# MotorCell.net
KiCad netlist of a schematic drawn in Altium Designer
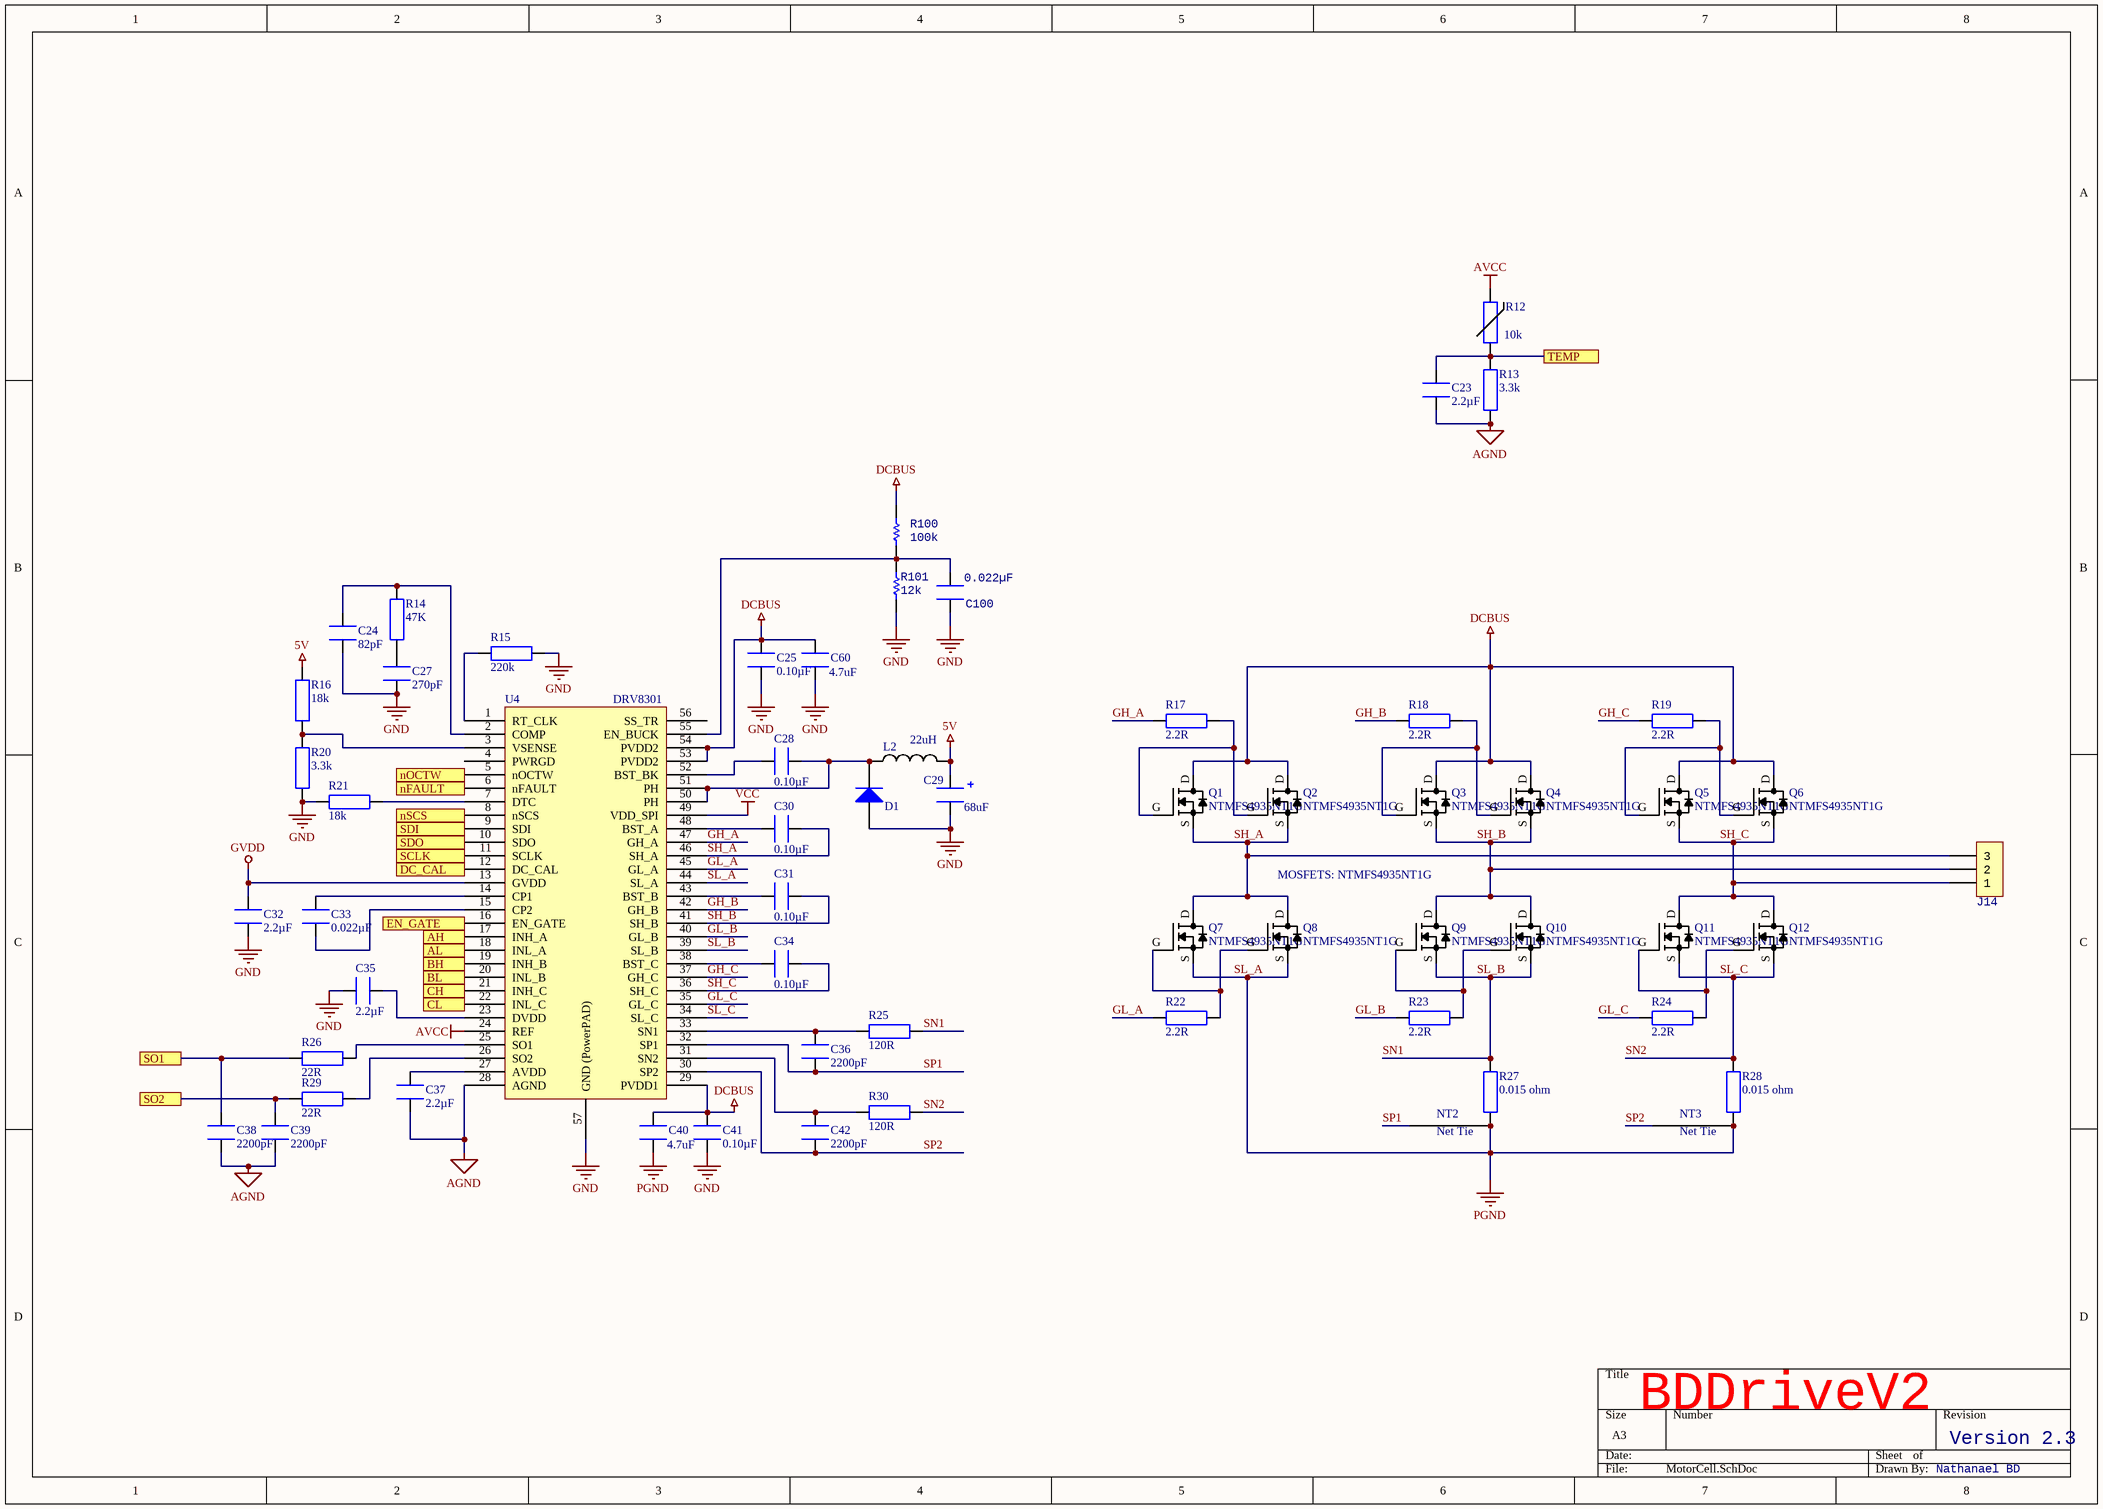
[diagram p0: MotorCell.SchDoc]

(export (version "E")
  (design (tool "Eeschema 10.0.6"))
  (components
    (comp (ref "C23")
      (value "2.2µF")
      (footprint "CAPC1608X09L")
      (description "CAP CER 2.2UF 16V X5R 0603")
      (fields
        (field (name "MANUFACTURER") "Murata Electronics North America")
        (field (name "MANUFACTURER PART NUMBER") "GRM188R61C225KE15D")
      )
      (libsource (lib "CustomComponents") (part "GRM188R61C225KE15D"))
    )
    (comp (ref "C24")
      (value "82pF")
      (footprint "CAPC1608X09L")
      (description "CAP CER 82PF 100V NP0 0603")
      (fields
        (field (name "MANUFACTURER") "Murata Electronics North America")
        (field (name "MANUFACTURER PART NUMBER") "GRM1885C2A820JA01D")
      )
      (libsource (lib "CustomComponents") (part "GRM1885C2A820JA01D"))
    )
    (comp (ref "C25")
      (value "0.10µF")
      (footprint "CAPC1608X09L")
      (description "CAP CER 0.1UF 25V X7R 0603")
      (fields
        (field (name "MANUFACTURER") "Murata Electronics North America")
        (field (name "MANUFACTURER PART NUMBER") "GRM188R71E104KA01D")
      )
      (libsource (lib "CustomComponents") (part "GRM188R71E104KA01D"))
    )
    (comp (ref "C27")
      (value "270pF")
      (footprint "CAPC1608X09L")
      (description "CAP CER 270PF 50V NP0 0603")
      (fields
        (field (name "MANUFACTURER") "Murata Electronics North America")
        (field (name "MANUFACTURER PART NUMBER") "GRM1885C1H271JA01D")
      )
      (libsource (lib "CustomComponents") (part "GRM1885C1H271JA01D"))
    )
    (comp (ref "C28")
      (value "0.10µF")
      (footprint "CAPC1608X09L")
      (description "CAP CER 0.1UF 25V X7R 0603")
      (fields
        (field (name "MANUFACTURER") "Murata Electronics North America")
        (field (name "MANUFACTURER PART NUMBER") "GRM188R71E104KA01D")
      )
      (libsource (lib "CustomComponents") (part "GRM188R71E104KA01D"))
    )
    (comp (ref "C29")
      (value "68uF")
      (footprint "CAPCP6032X28N")
      (description "CAP TANT 68UF 16V 20% 2312 250mOhm")
      (libsource (lib "CustomComponents") (part "T495C686M016ATE250"))
    )
    (comp (ref "C30")
      (value "0.10µF")
      (footprint "CAPC1608X09L")
      (description "CAP CER 0.1UF 25V X7R 0603")
      (fields
        (field (name "MANUFACTURER") "Murata Electronics North America")
        (field (name "MANUFACTURER PART NUMBER") "GRM188R71E104KA01D")
      )
      (libsource (lib "CustomComponents") (part "GRM188R71E104KA01D"))
    )
    (comp (ref "C31")
      (value "0.10µF")
      (footprint "CAPC1608X09L")
      (description "CAP CER 0.1UF 25V X7R 0603")
      (fields
        (field (name "MANUFACTURER") "Murata Electronics North America")
        (field (name "MANUFACTURER PART NUMBER") "GRM188R71E104KA01D")
      )
      (libsource (lib "CustomComponents") (part "GRM188R71E104KA01D"))
    )
    (comp (ref "C32")
      (value "2.2µF")
      (footprint "CAPC1608X09L")
      (description "CAP CER 2.2UF 16V X5R 0603")
      (fields
        (field (name "MANUFACTURER") "Murata Electronics North America")
        (field (name "MANUFACTURER PART NUMBER") "GRM188R61C225KE15D")
      )
      (libsource (lib "CustomComponents") (part "GRM188R61C225KE15D"))
    )
    (comp (ref "C33")
      (value "0.022µF")
      (footprint "CAPC1608X09L")
      (description "CAP CER 0.022UF 25V X7R 0603")
      (fields
        (field (name "MANUFACTURER") "Murata Electronics North America")
        (field (name "MANUFACTURER PART NUMBER") "GRM188R71E223KA01D")
      )
      (libsource (lib "CustomComponents") (part "GRM188R71E223KA01D"))
    )
    (comp (ref "C34")
      (value "0.10µF")
      (footprint "CAPC1608X09L")
      (description "CAP CER 0.1UF 25V X7R 0603")
      (fields
        (field (name "MANUFACTURER") "Murata Electronics North America")
        (field (name "MANUFACTURER PART NUMBER") "GRM188R71E104KA01D")
      )
      (libsource (lib "CustomComponents") (part "GRM188R71E104KA01D"))
    )
    (comp (ref "C35")
      (value "2.2µF")
      (footprint "CAPC1608X09L")
      (description "CAP CER 2.2UF 16V X5R 0603")
      (fields
        (field (name "MANUFACTURER") "Murata Electronics North America")
        (field (name "MANUFACTURER PART NUMBER") "GRM188R61C225KE15D")
      )
      (libsource (lib "CustomComponents") (part "GRM188R61C225KE15D"))
    )
    (comp (ref "C36")
      (value "2200pF")
      (footprint "CAPC1608X09L")
      (description "CAP CER 2200PF 50V NP0 0603")
      (fields
        (field (name "MANUFACTURER") "Murata Electronics North America")
        (field (name "TOLERANCE") "±5%")
      )
      (libsource (lib "CustomComponents") (part "GRM1885C1H222JA01D"))
    )
    (comp (ref "C37")
      (value "2.2µF")
      (footprint "CAPC1608X09L")
      (description "CAP CER 2.2UF 16V X5R 0603")
      (fields
        (field (name "MANUFACTURER") "Murata Electronics North America")
        (field (name "MANUFACTURER PART NUMBER") "GRM188R61C225KE15D")
      )
      (libsource (lib "CustomComponents") (part "GRM188R61C225KE15D"))
    )
    (comp (ref "C38")
      (value "2200pF")
      (footprint "CAPC1608X09L")
      (description "CAP CER 2200PF 50V NP0 0603")
      (fields
        (field (name "MANUFACTURER") "Murata Electronics North America")
        (field (name "TOLERANCE") "±5%")
      )
      (libsource (lib "CustomComponents") (part "GRM1885C1H222JA01D"))
    )
    (comp (ref "C39")
      (value "2200pF")
      (footprint "CAPC1608X09L")
      (description "CAP CER 2200PF 50V NP0 0603")
      (fields
        (field (name "MANUFACTURER") "Murata Electronics North America")
        (field (name "TOLERANCE") "±5%")
      )
      (libsource (lib "CustomComponents") (part "GRM1885C1H222JA01D"))
    )
    (comp (ref "C40")
      (value "4.7uF")
      (footprint "CAPC2012X09N")
      (description "CAP CER 4.7UF 35V X5R 0805")
      (libsource (lib "CustomComponents") (part "GRM219R6YA475KA73D"))
    )
    (comp (ref "C41")
      (value "0.10µF")
      (footprint "CAPC1608X09L")
      (description "CAP CER 0.1UF 25V X7R 0603")
      (fields
        (field (name "MANUFACTURER") "Murata Electronics North America")
        (field (name "MANUFACTURER PART NUMBER") "GRM188R71E104KA01D")
      )
      (libsource (lib "CustomComponents") (part "GRM188R71E104KA01D"))
    )
    (comp (ref "C42")
      (value "2200pF")
      (footprint "CAPC1608X09L")
      (description "CAP CER 2200PF 50V NP0 0603")
      (fields
        (field (name "MANUFACTURER") "Murata Electronics North America")
        (field (name "TOLERANCE") "±5%")
      )
      (libsource (lib "CustomComponents") (part "GRM1885C1H222JA01D"))
    )
    (comp (ref "C60")
      (value "4.7uF")
      (footprint "CAPC2012X09N")
      (description "CAP CER 4.7UF 35V X5R 0805")
      (libsource (lib "CustomComponents") (part "GRM219R6YA475KA73D"))
    )
    (comp (ref "C100")
      (value "0.022µF")
      (footprint "CAPC1608X09L")
      (description "CAP CER 0.022UF 25V X7R 0603")
      (fields
        (field (name "MANUFACTURER") "Murata Electronics North America")
        (field (name "MANUFACTURER PART NUMBER") "GRM188R71E223KA01D")
      )
      (libsource (lib "CustomComponents") (part "GRM188R71E223KA01D"))
    )
    (comp (ref "D1")
      (value "~")
      (footprint "DIOM2717X10N")
      (description "Rectifier Diode, Single, 40 V, 1 A, SOD-123FL, 2, 550 mV")
      (libsource (lib "CustomComponents") (part "MBR140SFT1G"))
    )
    (comp (ref "J14")
      (value "0436500327")
      (footprint "0436500327")
      (description "CONN HEADER 3POS VERT TIN T/H")
      (fields
        (field (name "MANUFACTURER") "Molex Connector Corporation")
        (field (name "MANUFACTURER PART NUMBER") "43650-0303")
      )
      (libsource (lib "CustomComponents") (part "0436500327"))
    )
    (comp (ref "L2")
      (value "22uH")
      (footprint "INDC6060X28N")
      (description "INDUCTOR 22UH 1.4A 175.5 MOHM")
      (libsource (lib "CustomComponents") (part "NR6028T220M"))
    )
    (comp (ref "NT2")
      (value "0.25mm")
      (footprint "NetTie_0.25mm")
      (libsource (lib "CustomComponents") (part "NetTie_0.25mm"))
    )
    (comp (ref "NT3")
      (value "0.25mm")
      (footprint "NetTie_0.25mm")
      (libsource (lib "CustomComponents") (part "NetTie_0.25mm"))
    )
    (comp (ref "Q1")
      (value "NTMFS4935NT1G")
      (footprint "SO8FL")
      (description "MOSFET N-CH 30V 13A SO8FL")
      (fields (field (name "MANUFACTURER") "ON Semiconductor"))
      (libsource (lib "CustomComponents") (part "NTMFS4935NT1G"))
    )
    (comp (ref "Q2")
      (value "NTMFS4935NT1G")
      (footprint "SO8FL_FILL")
      (description "MOSFET N-CH 30V 13A SO8FL")
      (fields (field (name "MANUFACTURER") "ON Semiconductor"))
      (libsource (lib "CustomComponents") (part "NTMFS4935NT1G"))
    )
    (comp (ref "Q3")
      (value "NTMFS4935NT1G")
      (footprint "SO8FL")
      (description "MOSFET N-CH 30V 13A SO8FL")
      (fields (field (name "MANUFACTURER") "ON Semiconductor"))
      (libsource (lib "CustomComponents") (part "NTMFS4935NT1G"))
    )
    (comp (ref "Q4")
      (value "NTMFS4935NT1G")
      (footprint "SO8FL_FILL")
      (description "MOSFET N-CH 30V 13A SO8FL")
      (fields (field (name "MANUFACTURER") "ON Semiconductor"))
      (libsource (lib "CustomComponents") (part "NTMFS4935NT1G"))
    )
    (comp (ref "Q5")
      (value "NTMFS4935NT1G")
      (footprint "SO8FL")
      (description "MOSFET N-CH 30V 13A SO8FL")
      (fields (field (name "MANUFACTURER") "ON Semiconductor"))
      (libsource (lib "CustomComponents") (part "NTMFS4935NT1G"))
    )
    (comp (ref "Q6")
      (value "NTMFS4935NT1G")
      (footprint "SO8FL_FILL")
      (description "MOSFET N-CH 30V 13A SO8FL")
      (fields (field (name "MANUFACTURER") "ON Semiconductor"))
      (libsource (lib "CustomComponents") (part "NTMFS4935NT1G"))
    )
    (comp (ref "Q7")
      (value "NTMFS4935NT1G")
      (footprint "SO8FL")
      (description "MOSFET N-CH 30V 13A SO8FL")
      (fields (field (name "MANUFACTURER") "ON Semiconductor"))
      (libsource (lib "CustomComponents") (part "NTMFS4935NT1G"))
    )
    (comp (ref "Q8")
      (value "NTMFS4935NT1G")
      (footprint "SO8FL")
      (description "MOSFET N-CH 30V 13A SO8FL")
      (fields (field (name "MANUFACTURER") "ON Semiconductor"))
      (libsource (lib "CustomComponents") (part "NTMFS4935NT1G"))
    )
    (comp (ref "Q9")
      (value "NTMFS4935NT1G")
      (footprint "SO8FL")
      (description "MOSFET N-CH 30V 13A SO8FL")
      (fields (field (name "MANUFACTURER") "ON Semiconductor"))
      (libsource (lib "CustomComponents") (part "NTMFS4935NT1G"))
    )
    (comp (ref "Q10")
      (value "NTMFS4935NT1G")
      (footprint "SO8FL")
      (description "MOSFET N-CH 30V 13A SO8FL")
      (fields (field (name "MANUFACTURER") "ON Semiconductor"))
      (libsource (lib "CustomComponents") (part "NTMFS4935NT1G"))
    )
    (comp (ref "Q11")
      (value "NTMFS4935NT1G")
      (footprint "SO8FL")
      (description "MOSFET N-CH 30V 13A SO8FL")
      (fields (field (name "MANUFACTURER") "ON Semiconductor"))
      (libsource (lib "CustomComponents") (part "NTMFS4935NT1G"))
    )
    (comp (ref "Q12")
      (value "NTMFS4935NT1G")
      (footprint "SO8FL")
      (description "MOSFET N-CH 30V 13A SO8FL")
      (fields (field (name "MANUFACTURER") "ON Semiconductor"))
      (libsource (lib "CustomComponents") (part "NTMFS4935NT1G"))
    )
    (comp (ref "R12")
      (value "10k")
      (footprint "RESC1005X40N")
      (description "THERMISTOR 10K OHM NTC 0402 SMD")
      (fields (field (name "Comment") "NCP15XH103F03RC"))
      (libsource (lib "CustomComponents") (part "NCP15XH103F03RC"))
    )
    (comp (ref "R13")
      (value "3.3k")
      (footprint "RESC1608X55N")
      (description "RES SMD 3.3K OHM 1% 1/10W 0603")
      (fields
        (field (name "MANUFACTURER") "Yageo")
        (field (name "MANUFACTURER PART NUMBER") "RC0603FR-073K3L")
      )
      (libsource (lib "CustomComponents") (part "RC0603FR-073K3L"))
    )
    (comp (ref "R14")
      (value "47K")
      (footprint "RESC1608X55N")
      (description "RES SMD 47K OHM 1% 1/10W 0603")
      (fields
        (field (name "MANUFACTURER") "Yageo")
        (field (name "MANUFACTURER PART NUMBER") "RC0603FR-0747KL")
      )
      (libsource (lib "CustomComponents") (part "RC0603FR-0747KL"))
    )
    (comp (ref "R15")
      (value "220k")
      (footprint "RESC1608X55N")
      (description "RES SMD 220K OHM 1% 1/10W 0603")
      (fields
        (field (name "MANUFACTURER") "Yageo")
        (field (name "MANUFACTURER PART NUMBER") "RC0603FR-07220KL")
      )
      (libsource (lib "CustomComponents") (part "RC0603FR-07220KL"))
    )
    (comp (ref "R16")
      (value "18k")
      (footprint "RESC1608X55N")
      (description "RES SMD 18K OHM 1% 1/10W 0603")
      (fields
        (field (name "MANUFACTURER") "Yageo")
        (field (name "MANUFACTURER PART NUMBER") "RC0603FR-0718KL")
      )
      (libsource (lib "CustomComponents") (part "RC0603FR-0718KL"))
    )
    (comp (ref "R17")
      (value "2.2R")
      (footprint "RESC1608X55N")
      (description "RES SMD 2.2 OHM 1% 1/10W 0603")
      (fields
        (field (name "MANUFACTURER") "Yageo")
        (field (name "MANUFACTURER PART NUMBER") "RC0603FR-072R2L")
      )
      (libsource (lib "CustomComponents") (part "RC0603FR-072R2L"))
    )
    (comp (ref "R18")
      (value "2.2R")
      (footprint "RESC1608X55N")
      (description "RES SMD 2.2 OHM 1% 1/10W 0603")
      (fields
        (field (name "MANUFACTURER") "Yageo")
        (field (name "MANUFACTURER PART NUMBER") "RC0603FR-072R2L")
      )
      (libsource (lib "CustomComponents") (part "RC0603FR-072R2L"))
    )
    (comp (ref "R19")
      (value "2.2R")
      (footprint "RESC1608X55N")
      (description "RES SMD 2.2 OHM 1% 1/10W 0603")
      (fields
        (field (name "MANUFACTURER") "Yageo")
        (field (name "MANUFACTURER PART NUMBER") "RC0603FR-072R2L")
      )
      (libsource (lib "CustomComponents") (part "RC0603FR-072R2L"))
    )
    (comp (ref "R20")
      (value "3.3k")
      (footprint "RESC1608X55N")
      (description "RES SMD 3.3K OHM 1% 1/10W 0603")
      (fields
        (field (name "MANUFACTURER") "Yageo")
        (field (name "MANUFACTURER PART NUMBER") "RC0603FR-073K3L")
      )
      (libsource (lib "CustomComponents") (part "RC0603FR-073K3L"))
    )
    (comp (ref "R21")
      (value "18k")
      (footprint "RESC1608X55N")
      (description "RES SMD 18K OHM 1% 1/10W 0603")
      (fields
        (field (name "MANUFACTURER") "Yageo")
        (field (name "MANUFACTURER PART NUMBER") "RC0603FR-0718KL")
      )
      (libsource (lib "CustomComponents") (part "RC0603FR-0718KL"))
    )
    (comp (ref "R22")
      (value "2.2R")
      (footprint "RESC1608X55N")
      (description "RES SMD 2.2 OHM 1% 1/10W 0603")
      (fields
        (field (name "MANUFACTURER") "Yageo")
        (field (name "MANUFACTURER PART NUMBER") "RC0603FR-072R2L")
      )
      (libsource (lib "CustomComponents") (part "RC0603FR-072R2L"))
    )
    (comp (ref "R23")
      (value "2.2R")
      (footprint "RESC1608X55N")
      (description "RES SMD 2.2 OHM 1% 1/10W 0603")
      (fields
        (field (name "MANUFACTURER") "Yageo")
        (field (name "MANUFACTURER PART NUMBER") "RC0603FR-072R2L")
      )
      (libsource (lib "CustomComponents") (part "RC0603FR-072R2L"))
    )
    (comp (ref "R24")
      (value "2.2R")
      (footprint "RESC1608X55N")
      (description "RES SMD 2.2 OHM 1% 1/10W 0603")
      (fields
        (field (name "MANUFACTURER") "Yageo")
        (field (name "MANUFACTURER PART NUMBER") "RC0603FR-072R2L")
      )
      (libsource (lib "CustomComponents") (part "RC0603FR-072R2L"))
    )
    (comp (ref "R25")
      (value "120R")
      (footprint "RESC1608X55N")
      (description "RES SMD 120 OHM 1% 1/10W 0603")
      (fields
        (field (name "MANUFACTURER") "Yageo")
        (field (name "MANUFACTURER PART NUMBER") "RC0603FR-07120RL")
      )
      (libsource (lib "CustomComponents") (part "RC0603FR-07120RL"))
    )
    (comp (ref "R26")
      (value "22R")
      (footprint "RESC1608X55N")
      (description "RES SMD 22 OHM 1% 1/10W 0603")
      (fields
        (field (name "MANUFACTURER") "Yageo")
        (field (name "MANUFACTURER PART NUMBER") "RC0603FR-0722RL")
      )
      (libsource (lib "CustomComponents") (part "RC0603FR-0722RL"))
    )
    (comp (ref "R27")
      (value "0.015 ohm")
      (footprint "RESC6432X09N")
      (description "RES SMD 0.015OHM 1% 3W 2512")
      (fields (field (name "Comment") "CSR2512C0R015F"))
      (libsource (lib "CustomComponents") (part "CSR2512C0R015F"))
    )
    (comp (ref "R28")
      (value "0.015 ohm")
      (footprint "RESC6432X09N")
      (description "RES SMD 0.015OHM 1% 3W 2512")
      (fields (field (name "Comment") "CSR2512C0R015F"))
      (libsource (lib "CustomComponents") (part "CSR2512C0R015F"))
    )
    (comp (ref "R29")
      (value "22R")
      (footprint "RESC1608X55N")
      (description "RES SMD 22 OHM 1% 1/10W 0603")
      (fields
        (field (name "MANUFACTURER") "Yageo")
        (field (name "MANUFACTURER PART NUMBER") "RC0603FR-0722RL")
      )
      (libsource (lib "CustomComponents") (part "RC0603FR-0722RL"))
    )
    (comp (ref "R30")
      (value "120R")
      (footprint "RESC1608X55N")
      (description "RES SMD 120 OHM 1% 1/10W 0603")
      (fields
        (field (name "MANUFACTURER") "Yageo")
        (field (name "MANUFACTURER PART NUMBER") "RC0603FR-07120RL")
      )
      (libsource (lib "CustomComponents") (part "RC0603FR-07120RL"))
    )
    (comp (ref "R100")
      (value "100k")
      (footprint "0603")
      (description "RES SMD 100K OHM 1% 1/10W 0603")
      (fields
        (field (name "MANUFACTURER") "Panasonic Electronic Components")
        (field (name "MANUFACTURER PART NUMBER") "ERJ-3EKF1003V")
      )
      (libsource (lib "CustomComponents") (part "ERJ-3EKF1003V"))
    )
    (comp (ref "R101")
      (value "12k")
      (footprint "0603")
      (description "RES SMD 12K OHM 1% 1/10W 0603")
      (fields
        (field (name "MANUFACTURER") "Panasonic Electronic Components")
        (field (name "MANUFACTURER PART NUMBER") "ERJ-3EKF1202V")
      )
      (libsource (lib "*") (part "ERJ-3EKF1202V"))
    )
    (comp (ref "U4")
      (value "~")
      (footprint "TSSOP50P810X120_HS-57N")
      (description "MOTOR DRIVER, 3PH, 56HTSSOP")
      (fields (field (name "PARTNUMBER") "DRV8301"))
      (libsource (lib "CustomComponents") (part "DRV8301"))
    )
  )
  (nets
    (net (code "1") (name "/AH") (class "Default")
      (node (ref "U4") (pin "17") (pinfunction "INH_A_17") (pintype "passive"))
    )
    (net (code "2") (name "/AL") (class "Default")
      (node (ref "U4") (pin "18") (pinfunction "INL_A_18") (pintype "passive"))
    )
    (net (code "3") (name "/BH") (class "Default")
      (node (ref "U4") (pin "19") (pinfunction "INH_B_19") (pintype "passive"))
    )
    (net (code "4") (name "/BL") (class "Default")
      (node (ref "U4") (pin "20") (pinfunction "INL_B_20") (pintype "passive"))
    )
    (net (code "5") (name "/CH") (class "Default")
      (node (ref "U4") (pin "21") (pinfunction "INH_C_21") (pintype "passive"))
    )
    (net (code "6") (name "/CL") (class "Default")
      (node (ref "U4") (pin "22") (pinfunction "INL_C_22") (pintype "passive"))
    )
    (net (code "7") (name "/DC_CAL") (class "Default")
      (node (ref "U4") (pin "12") (pinfunction "DC_CAL_12") (pintype "passive"))
    )
    (net (code "8") (name "/EN_GATE") (class "Default")
      (node (ref "U4") (pin "16") (pinfunction "EN_GATE_16") (pintype "passive"))
    )
    (net (code "9") (name "/GH_A") (class "Default")
      (node (ref "R17") (pin "2") (pinfunction "0_2") (pintype "passive"))
      (node (ref "U4") (pin "47") (pinfunction "GH_A_47") (pintype "passive"))
    )
    (net (code "10") (name "/GH_B") (class "Default")
      (node (ref "R18") (pin "2") (pinfunction "0_2") (pintype "passive"))
      (node (ref "U4") (pin "42") (pinfunction "GH_B_42") (pintype "passive"))
    )
    (net (code "11") (name "/GH_C") (class "Default")
      (node (ref "R19") (pin "2") (pinfunction "0_2") (pintype "passive"))
      (node (ref "U4") (pin "37") (pinfunction "GH_C_37") (pintype "passive"))
    )
    (net (code "12") (name "/GL_A") (class "Default")
      (node (ref "R22") (pin "2") (pinfunction "0_2") (pintype "passive"))
      (node (ref "U4") (pin "45") (pinfunction "GL_A_45") (pintype "passive"))
    )
    (net (code "13") (name "/GL_B") (class "Default")
      (node (ref "R23") (pin "2") (pinfunction "0_2") (pintype "passive"))
      (node (ref "U4") (pin "40") (pinfunction "GL_B_40") (pintype "passive"))
    )
    (net (code "14") (name "/GL_C") (class "Default")
      (node (ref "R24") (pin "2") (pinfunction "0_2") (pintype "passive"))
      (node (ref "U4") (pin "35") (pinfunction "GL_C_35") (pintype "passive"))
    )
    (net (code "15") (name "/SCLK") (class "Default")
      (node (ref "U4") (pin "11") (pinfunction "SCLK_11") (pintype "passive"))
    )
    (net (code "16") (name "/SDI") (class "Default")
      (node (ref "U4") (pin "9") (pinfunction "SDI_9") (pintype "passive"))
    )
    (net (code "17") (name "/SDO") (class "Default")
      (node (ref "U4") (pin "10") (pinfunction "SDO_10") (pintype "passive"))
    )
    (net (code "18") (name "/SH_A") (class "Default")
      (node (ref "C30") (pin "1") (pinfunction "1_1") (pintype "passive"))
      (node (ref "J14") (pin "3") (pinfunction "3_3") (pintype "passive"))
      (node (ref "Q1") (pin "S") (pinfunction "S_S") (pintype "passive"))
      (node (ref "Q2") (pin "S") (pinfunction "S_S") (pintype "passive"))
      (node (ref "Q7") (pin "D") (pinfunction "D_D") (pintype "passive"))
      (node (ref "Q8") (pin "D") (pinfunction "D_D") (pintype "passive"))
      (node (ref "U4") (pin "46") (pinfunction "SH_A_46") (pintype "passive"))
    )
    (net (code "19") (name "/SH_B") (class "Default")
      (node (ref "C31") (pin "1") (pinfunction "1_1") (pintype "passive"))
      (node (ref "J14") (pin "2") (pinfunction "2_2") (pintype "passive"))
      (node (ref "Q10") (pin "D") (pinfunction "D_D") (pintype "passive"))
      (node (ref "Q3") (pin "S") (pinfunction "S_S") (pintype "passive"))
      (node (ref "Q4") (pin "S") (pinfunction "S_S") (pintype "passive"))
      (node (ref "Q9") (pin "D") (pinfunction "D_D") (pintype "passive"))
      (node (ref "U4") (pin "41") (pinfunction "SH_B_41") (pintype "passive"))
    )
    (net (code "20") (name "/SH_C") (class "Default")
      (node (ref "C34") (pin "1") (pinfunction "1_1") (pintype "passive"))
      (node (ref "J14") (pin "1") (pinfunction "1_1") (pintype "passive"))
      (node (ref "Q11") (pin "D") (pinfunction "D_D") (pintype "passive"))
      (node (ref "Q12") (pin "D") (pinfunction "D_D") (pintype "passive"))
      (node (ref "Q5") (pin "S") (pinfunction "S_S") (pintype "passive"))
      (node (ref "Q6") (pin "S") (pinfunction "S_S") (pintype "passive"))
      (node (ref "U4") (pin "36") (pinfunction "SH_C_36") (pintype "passive"))
    )
    (net (code "21") (name "/SL_B") (class "Default")
      (node (ref "Q10") (pin "S") (pinfunction "S_S") (pintype "passive"))
      (node (ref "Q9") (pin "S") (pinfunction "S_S") (pintype "passive"))
      (node (ref "R25") (pin "1") (pinfunction "0_1") (pintype "passive"))
      (node (ref "R27") (pin "2") (pinfunction "0_2") (pintype "passive"))
      (node (ref "U4") (pin "39") (pinfunction "SL_B_39") (pintype "passive"))
    )
    (net (code "22") (name "/SL_C") (class "Default")
      (node (ref "Q11") (pin "S") (pinfunction "S_S") (pintype "passive"))
      (node (ref "Q12") (pin "S") (pinfunction "S_S") (pintype "passive"))
      (node (ref "R28") (pin "2") (pinfunction "0_2") (pintype "passive"))
      (node (ref "R30") (pin "1") (pinfunction "0_1") (pintype "passive"))
      (node (ref "U4") (pin "34") (pinfunction "SL_C_34") (pintype "passive"))
    )
    (net (code "23") (name "/SO1") (class "Default")
      (node (ref "C38") (pin "1") (pinfunction "1_1") (pintype "passive"))
      (node (ref "R26") (pin "2") (pinfunction "0_2") (pintype "passive"))
    )
    (net (code "24") (name "/SO2") (class "Default")
      (node (ref "C39") (pin "1") (pinfunction "1_1") (pintype "passive"))
      (node (ref "R29") (pin "2") (pinfunction "0_2") (pintype "passive"))
    )
    (net (code "25") (name "/SP1") (class "Default")
      (node (ref "C36") (pin "2") (pinfunction "2_2") (pintype "passive"))
      (node (ref "NT2") (pin "1") (pintype "passive"))
      (node (ref "U4") (pin "32") (pinfunction "SP1_32") (pintype "passive"))
    )
    (net (code "26") (name "/SP2") (class "Default")
      (node (ref "C42") (pin "2") (pinfunction "2_2") (pintype "passive"))
      (node (ref "NT3") (pin "1") (pintype "passive"))
      (node (ref "U4") (pin "30") (pinfunction "SP2_30") (pintype "passive"))
    )
    (net (code "27") (name "/TEMP") (class "Default")
      (node (ref "C23") (pin "2") (pinfunction "2_2") (pintype "passive"))
      (node (ref "R12") (pin "1") (pinfunction "0_1") (pintype "passive"))
      (node (ref "R13") (pin "1") (pinfunction "0_1") (pintype "passive"))
    )
    (net (code "28") (name "/nFAULT") (class "Default")
      (node (ref "U4") (pin "6") (pinfunction "nFAULT_6") (pintype "passive"))
    )
    (net (code "29") (name "/nOCTW") (class "Default")
      (node (ref "U4") (pin "5") (pinfunction "nOCTW_5") (pintype "passive"))
    )
    (net (code "30") (name "/nSCS") (class "Default")
      (node (ref "U4") (pin "8") (pinfunction "nSCS_8") (pintype "passive"))
    )
    (net (code "31") (name "5V") (class "Default")
      (node (ref "C29") (pin "1") (pinfunction "1_1") (pintype "passive"))
      (node (ref "L2") (pin "2") (pinfunction "2_2") (pintype "passive"))
      (node (ref "R16") (pin "1") (pinfunction "0_1") (pintype "passive"))
    )
    (net (code "32") (name "AGND") (class "Default")
      (node (ref "C23") (pin "1") (pinfunction "1_1") (pintype "passive"))
      (node (ref "C37") (pin "1") (pinfunction "1_1") (pintype "passive"))
      (node (ref "C38") (pin "2") (pinfunction "2_2") (pintype "passive"))
      (node (ref "C39") (pin "2") (pinfunction "2_2") (pintype "passive"))
      (node (ref "R13") (pin "2") (pinfunction "0_2") (pintype "passive"))
      (node (ref "U4") (pin "28") (pinfunction "AGND_28") (pintype "passive"))
    )
    (net (code "33") (name "AVCC") (class "Default")
      (node (ref "R12") (pin "2") (pinfunction "0_2") (pintype "passive"))
      (node (ref "U4") (pin "24") (pinfunction "REF_24") (pintype "passive"))
    )
    (net (code "34") (name "DCBUS") (class "Default")
      (node (ref "C25") (pin "1") (pinfunction "1_1") (pintype "passive"))
      (node (ref "C40") (pin "2") (pinfunction "2_2") (pintype "passive"))
      (node (ref "C41") (pin "1") (pinfunction "1_1") (pintype "passive"))
      (node (ref "C60") (pin "2") (pinfunction "2_2") (pintype "passive"))
      (node (ref "Q1") (pin "D") (pinfunction "D_D") (pintype "passive"))
      (node (ref "Q2") (pin "D") (pinfunction "D_D") (pintype "passive"))
      (node (ref "Q3") (pin "D") (pinfunction "D_D") (pintype "passive"))
      (node (ref "Q4") (pin "D") (pinfunction "D_D") (pintype "passive"))
      (node (ref "Q5") (pin "D") (pinfunction "D_D") (pintype "passive"))
      (node (ref "Q6") (pin "D") (pinfunction "D_D") (pintype "passive"))
      (node (ref "R100") (pin "1") (pinfunction "1_1") (pintype "passive"))
      (node (ref "U4") (pin "29") (pinfunction "PVDD1_29") (pintype "passive"))
      (node (ref "U4") (pin "53") (pinfunction "PVDD2_53") (pintype "passive"))
      (node (ref "U4") (pin "54") (pinfunction "PVDD2_54") (pintype "passive"))
    )
    (net (code "35") (name "GND") (class "Default")
      (node (ref "C100") (pin "1") (pinfunction "1_1") (pintype "passive"))
      (node (ref "C24") (pin "2") (pinfunction "2_2") (pintype "passive"))
      (node (ref "C25") (pin "2") (pinfunction "2_2") (pintype "passive"))
      (node (ref "C27") (pin "2") (pinfunction "2_2") (pintype "passive"))
      (node (ref "C29") (pin "2") (pinfunction "2_2") (pintype "passive"))
      (node (ref "C32") (pin "1") (pinfunction "1_1") (pintype "passive"))
      (node (ref "C35") (pin "1") (pinfunction "1_1") (pintype "passive"))
      (node (ref "C41") (pin "2") (pinfunction "2_2") (pintype "passive"))
      (node (ref "C60") (pin "1") (pinfunction "1_1") (pintype "passive"))
      (node (ref "D1") (pin "A") (pinfunction "A_A") (pintype "passive"))
      (node (ref "R101") (pin "1") (pinfunction "1_1") (pintype "passive"))
      (node (ref "R15") (pin "2") (pinfunction "0_2") (pintype "passive"))
      (node (ref "R20") (pin "2") (pinfunction "0_2") (pintype "passive"))
      (node (ref "R21") (pin "2") (pinfunction "0_2") (pintype "passive"))
      (node (ref "U4") (pin "57") (pinfunction "GND_(PowerPAD)_57") (pintype "passive"))
    )
    (net (code "36") (name "GVDD") (class "Default")
      (node (ref "C32") (pin "2") (pinfunction "2_2") (pintype "passive"))
      (node (ref "U4") (pin "13") (pinfunction "GVDD_13") (pintype "passive"))
    )
    (net (code "37") (name "Net-(C27-Pad1)") (class "Default")
      (node (ref "C27") (pin "1") (pinfunction "1_1") (pintype "passive"))
      (node (ref "R14") (pin "2") (pinfunction "0_2") (pintype "passive"))
    )
    (net (code "38") (name "Net-(C28-Pad1)") (class "Default")
      (node (ref "C28") (pin "1") (pinfunction "1_1") (pintype "passive"))
      (node (ref "D1") (pin "K") (pinfunction "K_K") (pintype "passive"))
      (node (ref "L2") (pin "1") (pinfunction "1_1") (pintype "passive"))
      (node (ref "U4") (pin "50") (pinfunction "PH_50") (pintype "passive"))
      (node (ref "U4") (pin "51") (pinfunction "PH_51") (pintype "passive"))
    )
    (net (code "39") (name "Net-(Q1-PadG)") (class "Default")
      (node (ref "Q1") (pin "G") (pinfunction "G_G") (pintype "passive"))
      (node (ref "Q2") (pin "G") (pinfunction "G_G") (pintype "passive"))
      (node (ref "R17") (pin "1") (pinfunction "0_1") (pintype "passive"))
    )
    (net (code "40") (name "Net-(Q3-PadG)") (class "Default")
      (node (ref "Q3") (pin "G") (pinfunction "G_G") (pintype "passive"))
      (node (ref "Q4") (pin "G") (pinfunction "G_G") (pintype "passive"))
      (node (ref "R18") (pin "1") (pinfunction "0_1") (pintype "passive"))
    )
    (net (code "41") (name "Net-(Q5-PadG)") (class "Default")
      (node (ref "Q5") (pin "G") (pinfunction "G_G") (pintype "passive"))
      (node (ref "Q6") (pin "G") (pinfunction "G_G") (pintype "passive"))
      (node (ref "R19") (pin "1") (pinfunction "0_1") (pintype "passive"))
    )
    (net (code "42") (name "Net-(Q7-PadG)") (class "Default")
      (node (ref "Q7") (pin "G") (pinfunction "G_G") (pintype "passive"))
      (node (ref "Q8") (pin "G") (pinfunction "G_G") (pintype "passive"))
      (node (ref "R22") (pin "1") (pinfunction "0_1") (pintype "passive"))
    )
    (net (code "43") (name "Net-(Q10-PadG)") (class "Default")
      (node (ref "Q10") (pin "G") (pinfunction "G_G") (pintype "passive"))
      (node (ref "Q9") (pin "G") (pinfunction "G_G") (pintype "passive"))
      (node (ref "R23") (pin "1") (pinfunction "0_1") (pintype "passive"))
    )
    (net (code "44") (name "Net-(Q11-PadG)") (class "Default")
      (node (ref "Q11") (pin "G") (pinfunction "G_G") (pintype "passive"))
      (node (ref "Q12") (pin "G") (pinfunction "G_G") (pintype "passive"))
      (node (ref "R24") (pin "1") (pinfunction "0_1") (pintype "passive"))
    )
    (net (code "45") (name "Net-(U4-AVDD)") (class "Default")
      (node (ref "C37") (pin "2") (pinfunction "2_2") (pintype "passive"))
      (node (ref "U4") (pin "27") (pinfunction "AVDD_27") (pintype "passive"))
    )
    (net (code "46") (name "Net-(U4-BST_A)") (class "Default")
      (node (ref "C30") (pin "2") (pinfunction "2_2") (pintype "passive"))
      (node (ref "U4") (pin "48") (pinfunction "BST_A_48") (pintype "passive"))
    )
    (net (code "47") (name "Net-(U4-BST_B)") (class "Default")
      (node (ref "C31") (pin "2") (pinfunction "2_2") (pintype "passive"))
      (node (ref "U4") (pin "43") (pinfunction "BST_B_43") (pintype "passive"))
    )
    (net (code "48") (name "Net-(U4-BST_BK)") (class "Default")
      (node (ref "C28") (pin "2") (pinfunction "2_2") (pintype "passive"))
      (node (ref "U4") (pin "52") (pinfunction "BST_BK_52") (pintype "passive"))
    )
    (net (code "49") (name "Net-(U4-BST_C)") (class "Default")
      (node (ref "C34") (pin "2") (pinfunction "2_2") (pintype "passive"))
      (node (ref "U4") (pin "38") (pinfunction "BST_C_38") (pintype "passive"))
    )
    (net (code "50") (name "Net-(U4-COMP)") (class "Default")
      (node (ref "C24") (pin "1") (pinfunction "1_1") (pintype "passive"))
      (node (ref "R14") (pin "1") (pinfunction "0_1") (pintype "passive"))
      (node (ref "U4") (pin "2") (pinfunction "COMP_2") (pintype "passive"))
    )
    (net (code "51") (name "Net-(U4-CP1)") (class "Default")
      (node (ref "C33") (pin "1") (pinfunction "1_1") (pintype "passive"))
      (node (ref "U4") (pin "14") (pinfunction "CP1_14") (pintype "passive"))
    )
    (net (code "52") (name "Net-(U4-CP2)") (class "Default")
      (node (ref "C33") (pin "2") (pinfunction "2_2") (pintype "passive"))
      (node (ref "U4") (pin "15") (pinfunction "CP2_15") (pintype "passive"))
    )
    (net (code "53") (name "Net-(U4-DTC)") (class "Default")
      (node (ref "R21") (pin "1") (pinfunction "0_1") (pintype "passive"))
      (node (ref "U4") (pin "7") (pinfunction "DTC_7") (pintype "passive"))
    )
    (net (code "54") (name "Net-(U4-DVDD)") (class "Default")
      (node (ref "C35") (pin "2") (pinfunction "2_2") (pintype "passive"))
      (node (ref "U4") (pin "23") (pinfunction "DVDD_23") (pintype "passive"))
    )
    (net (code "55") (name "Net-(U4-EN_BUCK)") (class "Default")
      (node (ref "C100") (pin "2") (pinfunction "2_2") (pintype "passive"))
      (node (ref "R100") (pin "2") (pinfunction "2_2") (pintype "passive"))
      (node (ref "R101") (pin "2") (pinfunction "2_2") (pintype "passive"))
      (node (ref "U4") (pin "55") (pinfunction "EN_BUCK_55") (pintype "passive"))
    )
    (net (code "56") (name "Net-(U4-RT_CLK)") (class "Default")
      (node (ref "R15") (pin "1") (pinfunction "0_1") (pintype "passive"))
      (node (ref "U4") (pin "1") (pinfunction "RT_CLK_1") (pintype "passive"))
    )
    (net (code "57") (name "Net-(U4-SN1)") (class "Default")
      (node (ref "C36") (pin "1") (pinfunction "1_1") (pintype "passive"))
      (node (ref "R25") (pin "2") (pinfunction "0_2") (pintype "passive"))
      (node (ref "U4") (pin "33") (pinfunction "SN1_33") (pintype "passive"))
    )
    (net (code "58") (name "Net-(U4-SN2)") (class "Default")
      (node (ref "C42") (pin "1") (pinfunction "1_1") (pintype "passive"))
      (node (ref "R30") (pin "2") (pinfunction "0_2") (pintype "passive"))
      (node (ref "U4") (pin "31") (pinfunction "SN2_31") (pintype "passive"))
    )
    (net (code "59") (name "Net-(U4-SO1)") (class "Default")
      (node (ref "R26") (pin "1") (pinfunction "0_1") (pintype "passive"))
      (node (ref "U4") (pin "25") (pinfunction "SO1_25") (pintype "passive"))
    )
    (net (code "60") (name "Net-(U4-SO2)") (class "Default")
      (node (ref "R29") (pin "1") (pinfunction "0_1") (pintype "passive"))
      (node (ref "U4") (pin "26") (pinfunction "SO2_26") (pintype "passive"))
    )
    (net (code "61") (name "Net-(U4-VSENSE)") (class "Default")
      (node (ref "R16") (pin "2") (pinfunction "0_2") (pintype "passive"))
      (node (ref "R20") (pin "1") (pinfunction "0_1") (pintype "passive"))
      (node (ref "U4") (pin "3") (pinfunction "VSENSE_3") (pintype "passive"))
    )
    (net (code "62") (name "PGND") (class "Default")
      (node (ref "C40") (pin "1") (pinfunction "1_1") (pintype "passive"))
      (node (ref "NT2") (pin "2") (pintype "passive"))
      (node (ref "NT3") (pin "2") (pintype "passive"))
      (node (ref "Q7") (pin "S") (pinfunction "S_S") (pintype "passive"))
      (node (ref "Q8") (pin "S") (pinfunction "S_S") (pintype "passive"))
      (node (ref "R27") (pin "1") (pinfunction "0_1") (pintype "passive"))
      (node (ref "R28") (pin "1") (pinfunction "0_1") (pintype "passive"))
      (node (ref "U4") (pin "44") (pinfunction "SL_A_44") (pintype "passive"))
    )
    (net (code "63") (name "VCC") (class "Default")
      (node (ref "U4") (pin "49") (pinfunction "VDD_SPI_49") (pintype "passive"))
    )
    (net (code "64") (name "unconnected-(U4-PWRGD-Pad4)") (class "Default")
      (node (ref "U4") (pin "4") (pinfunction "PWRGD_4") (pintype "passive"))
    )
    (net (code "65") (name "unconnected-(U4-SS_TR-Pad56)") (class "Default")
      (node (ref "U4") (pin "56") (pinfunction "SS_TR_56") (pintype "passive"))
    )
  )
)
